# OverTempProtection.net
KiCad netlist of a schematic drawn in Altium Designer
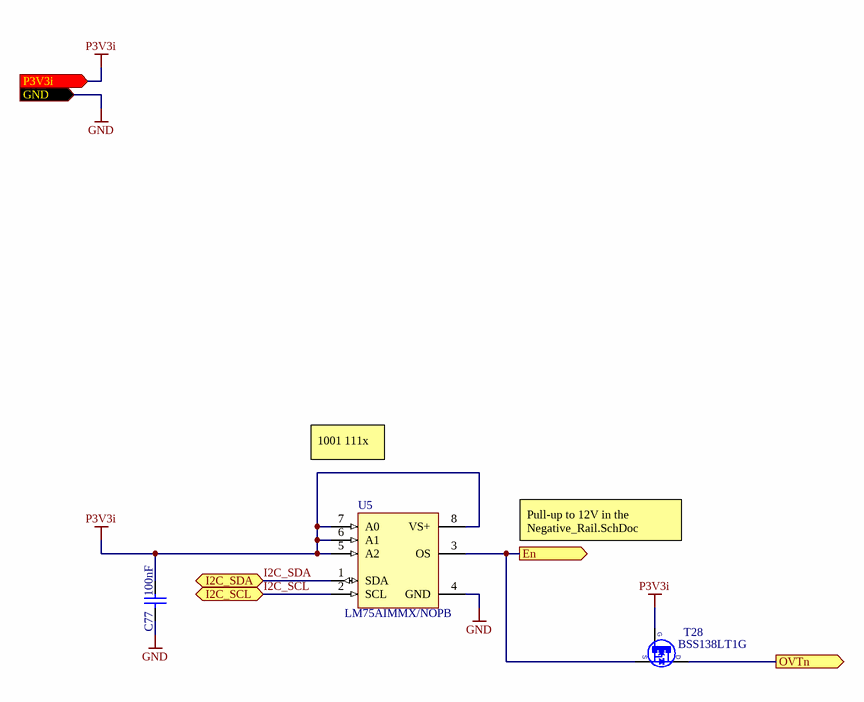
[diagram p0: OverTempProtection.SchDoc]

(export (version "E")
  (design (tool "Eeschema 10.0.6"))
  (components
    (comp (ref "C77")
      (value "100nF")
      (footprint "CAPC1608X87N")
      (description "Non-polarised capacitor")
      (fields
        (field (name "PART NUMBER") "CC0603_100NF_50V_10%_X7R")
        (field (name "VOLTAGE") "50V")
        (field (name "AUTHOR") "CERN DEM JLC")
      )
      (libsource (lib "Capacitors") (part "Capacitor - non polarized"))
    )
    (comp (ref "T28")
      (value "BSS138LT1G")
      (footprint "SOT95P240X110-3N")
      (description "N-CHANNEL MOSFET WITH DIODE")
      (fields
        (field (name "MANUFACTURER") "ON SEMICONDUCTOR")
        (field (name "MANUFACTURER PART NUMBER") "BSS138L")
        (field (name "AUTHOR") "CERN DEM JLC")
      )
      (libsource (lib "ICs And Semiconductors") (part "N-MOSFET-D 1G 2S 3D"))
    )
    (comp (ref "U5")
      (value "LM75AIMMX/NOPB")
      (footprint "DGK0008A_M")
      (description "Serial Switch/Digital Sensor, 9 Bit(s), 3Cel, Square, 8 Pin, Surface Mount")
      (libsource (lib "TechnoSystem Workspace") (part "SEN-TEMP-LM75-8"))
    )
  )
  (nets
    (net (code "1") (name "/En") (class "Default")
      (node (ref "T28") (pin "2") (pinfunction "S_2") (pintype "passive"))
      (node (ref "U5") (pin "3") (pinfunction "OS_3") (pintype "open_collector"))
    )
    (net (code "2") (name "/I2C_SCL") (class "Default")
      (node (ref "U5") (pin "2") (pinfunction "SCL_2") (pintype "input"))
    )
    (net (code "3") (name "/I2C_SDA") (class "Default")
      (node (ref "U5") (pin "1") (pinfunction "SDA_1") (pintype "bidirectional"))
    )
    (net (code "4") (name "/OVTn") (class "Default")
      (node (ref "T28") (pin "3") (pinfunction "D_3") (pintype "passive"))
    )
    (net (code "5") (name "GND") (class "Default")
      (node (ref "C77") (pin "1") (pinfunction "1_1") (pintype "passive"))
      (node (ref "U5") (pin "4") (pinfunction "GND_4") (pintype "power_in"))
    )
    (net (code "6") (name "P3V3i") (class "Default")
      (node (ref "C77") (pin "2") (pinfunction "2_2") (pintype "passive"))
      (node (ref "T28") (pin "1") (pinfunction "G_1") (pintype "passive"))
      (node (ref "U5") (pin "5") (pinfunction "A2_5") (pintype "input"))
      (node (ref "U5") (pin "6") (pinfunction "A1_6") (pintype "input"))
      (node (ref "U5") (pin "7") (pinfunction "A0_7") (pintype "input"))
      (node (ref "U5") (pin "8") (pinfunction "VS+_8") (pintype "power_in"))
    )
  )
)
